# ProPrj_ct_mini_board_2024-09-02.net
KiCad netlist of a schematic drawn in EasyEDA Pro
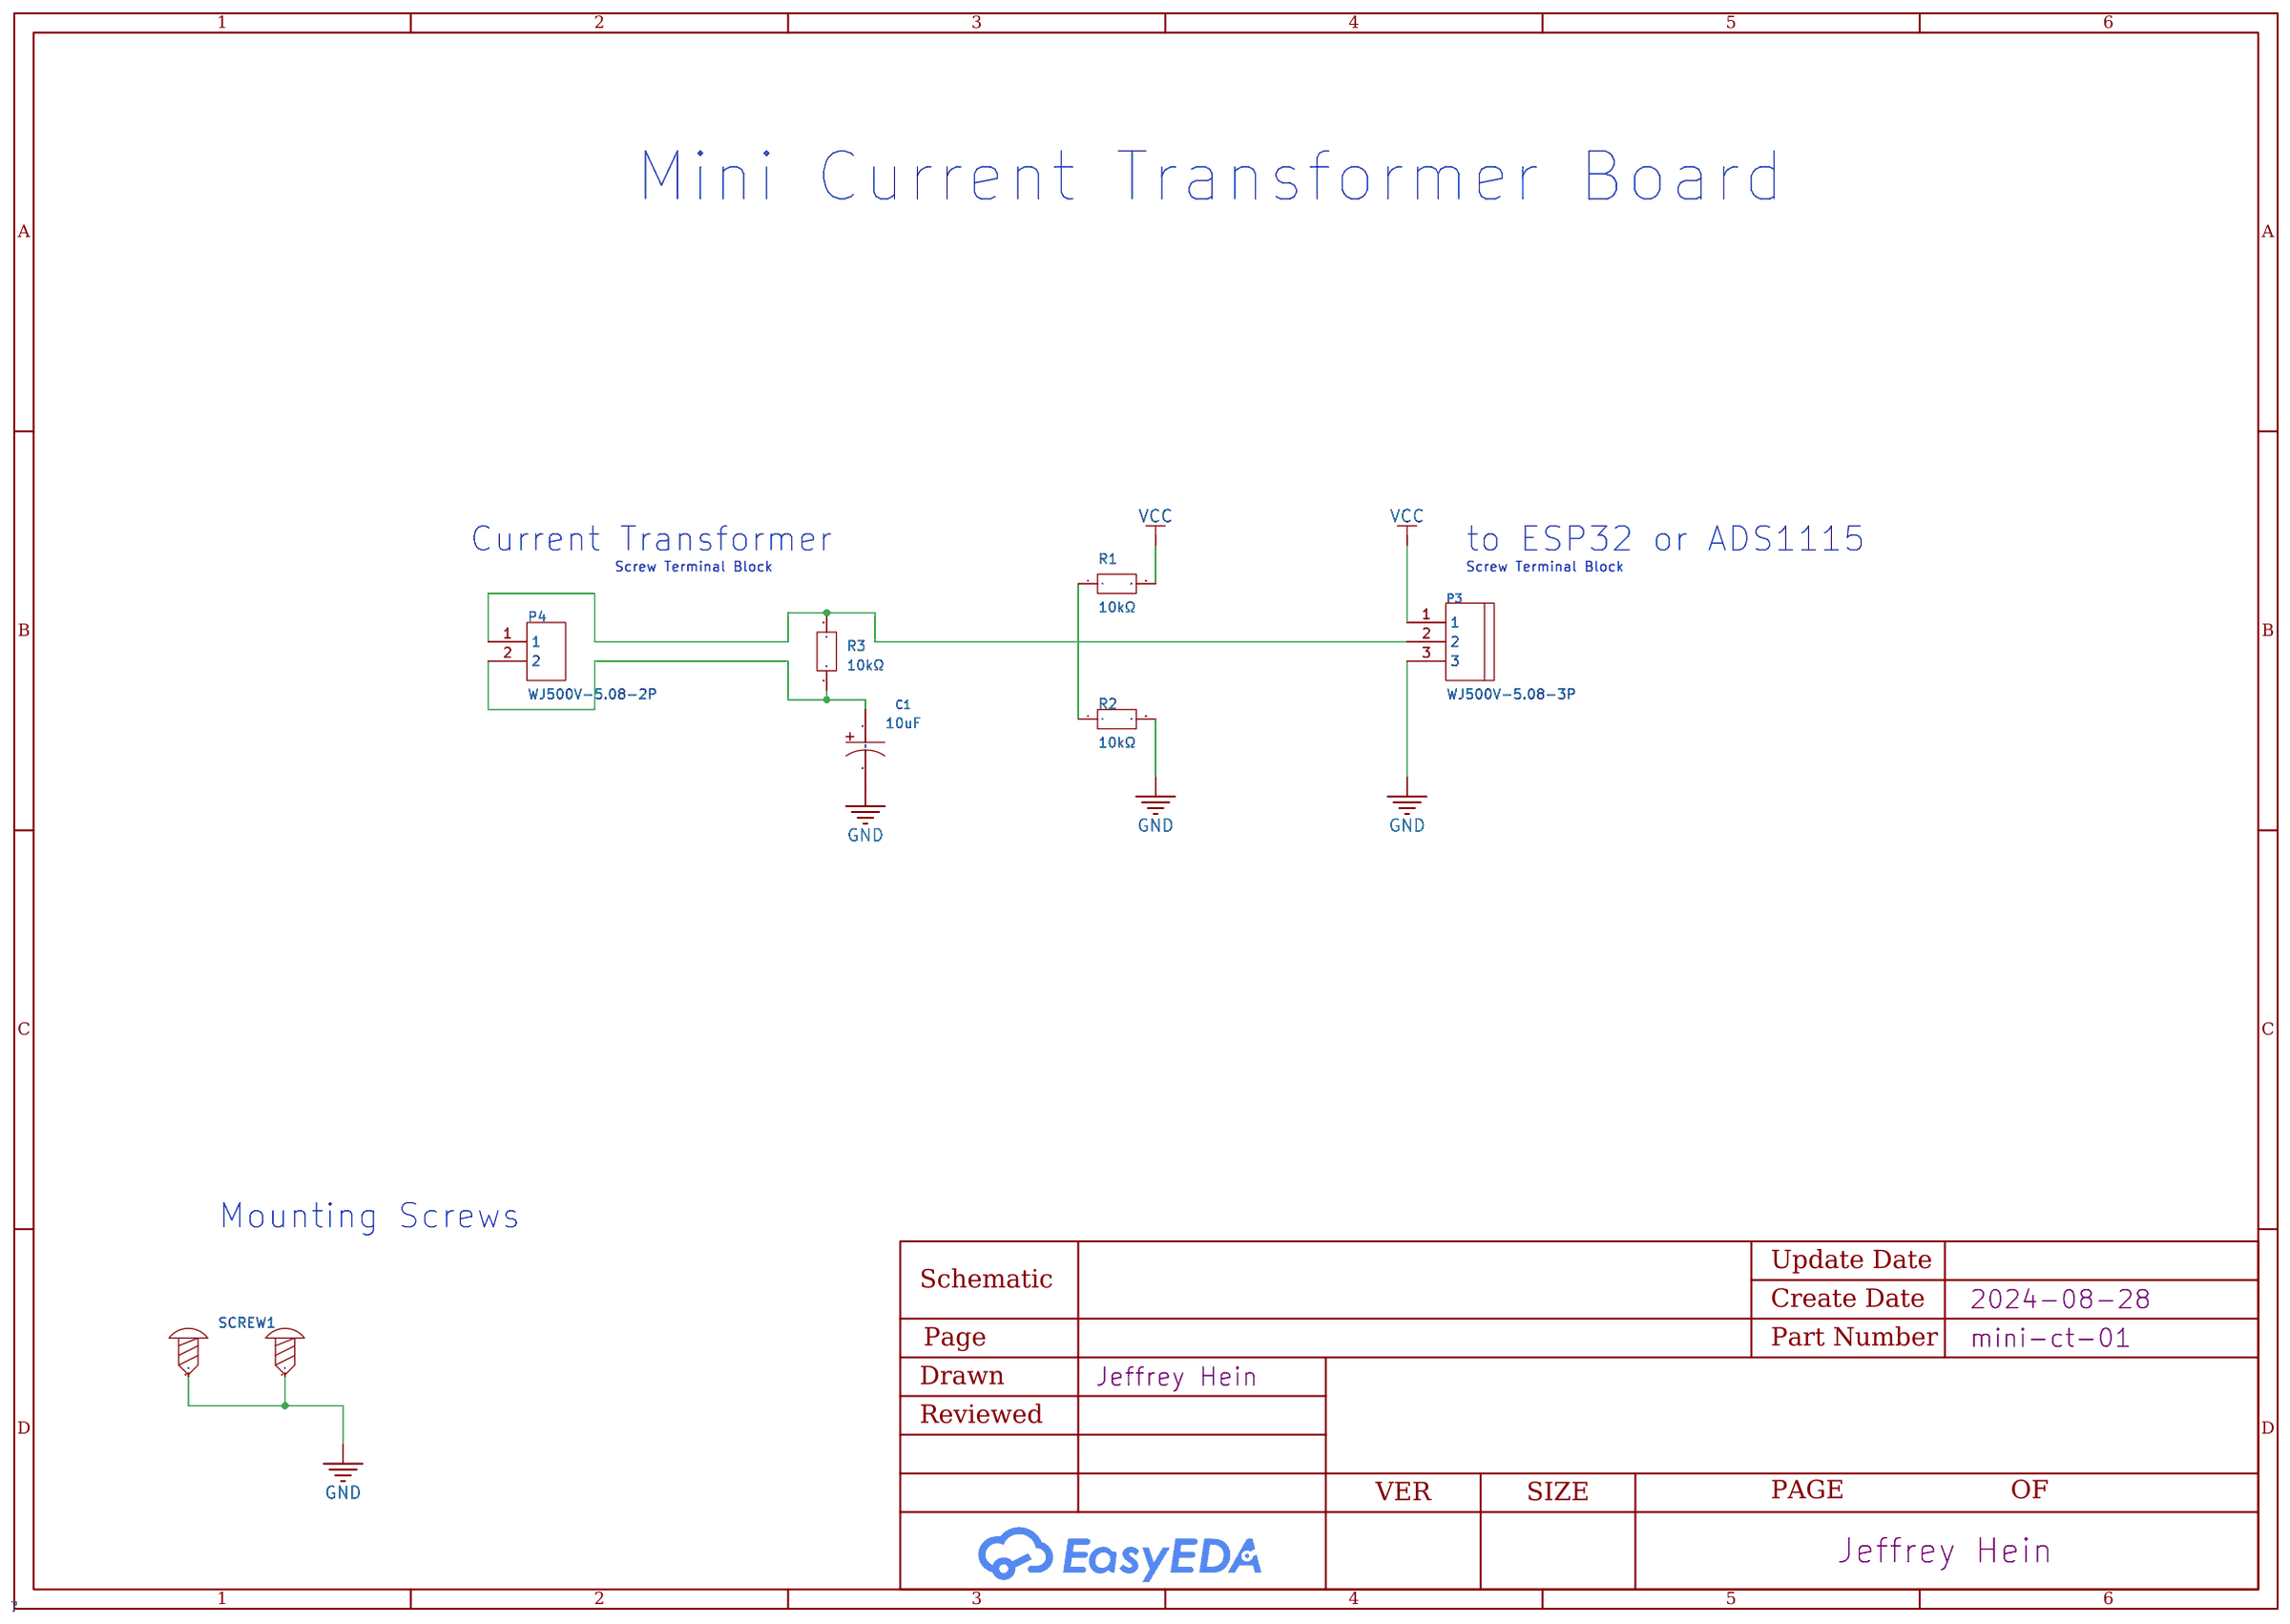
[diagram p0: schematic sheet]

(export (version "E")
  (design (tool "Eeschema 10.0.6"))
  (components
    (comp (ref "C1")
      (value "10uF")
      (footprint "easyedapro:CAP-TH_BD5.0-P5.00-D1.0-FD")
      (fields
        (field (name "Manufacturer Part") "UVZ1C100MDD1TA")
        (field (name "Manufacturer") "Nichicon(尼吉康)")
      )
      (libsource (lib "easyedapro") (part "UVZ1C100MDD1TA"))
    )
    (comp (ref "P3")
      (value "WJ500V-5.08-3P")
      (footprint "easyedapro:CONN-TH_3P-P5.00_WJ500V-5.08-3P")
      (fields (field (name "Manufacturer") "KANGNEX(康奈克斯电气)"))
      (libsource (lib "easyedapro") (part "WJ500V-5.08-3P-14-00A"))
    )
    (comp (ref "P4")
      (value "WJ500V-5.08-2P")
      (footprint "easyedapro:CONN-TH_2P-P5.00_WJ500V-5.08-2P")
      (fields (field (name "Manufacturer") "KANGNEX(康奈克斯电气)"))
      (libsource (lib "easyedapro") (part "WJ500V-5.08-2P-14-00A"))
    )
    (comp (ref "R1")
      (value "10kΩ")
      (footprint "easyedapro:RES-TH_BD2.4-L6.3-P10.30-D0.6")
      (fields
        (field (name "Manufacturer Part") "RN1/4W10KFT/BA1")
        (field (name "Manufacturer") "Tyohm(幸亚电阻)")
      )
      (libsource (lib "easyedapro") (part "RN 1/4W 10K F T/B A1"))
    )
    (comp (ref "R2")
      (value "10kΩ")
      (footprint "easyedapro:RES-TH_BD2.4-L6.3-P10.30-D0.6")
      (fields
        (field (name "Manufacturer Part") "RN1/4W10KFT/BA1")
        (field (name "Manufacturer") "Tyohm(幸亚电阻)")
      )
      (libsource (lib "easyedapro") (part "RN 1/4W 10K F T/B A1"))
    )
    (comp (ref "R3")
      (value "10kΩ")
      (footprint "easyedapro:RES-TH_BD2.4-L6.3-P10.30-D0.6")
      (fields
        (field (name "Manufacturer Part") "RN1/4W10KFT/BA1")
        (field (name "Manufacturer") "Tyohm(幸亚电阻)")
      )
      (libsource (lib "easyedapro") (part "RN 1/4W 10K F T/B A1"))
    )
    (comp (ref "SCREW1")
      (value "~")
      (footprint "easyedapro:Screw-Hole-M2")
      (libsource (lib "easyedapro") (part "Screw-Hole"))
    )
    (comp (ref "SCREW2")
      (value "~")
      (footprint "easyedapro:Screw-Hole-M2")
      (libsource (lib "easyedapro") (part "Screw-Hole"))
    )
  )
  (nets
    (net (code "1") (name "GND") (class "Default")
      (node (ref "C1") (pin "2") (pinfunction "2_2") (pintype "input"))
      (node (ref "P3") (pin "3") (pinfunction "3_3") (pintype "input"))
      (node (ref "R2") (pin "2") (pinfunction "2_2") (pintype "unspecified"))
      (node (ref "SCREW1") (pin "1") (pinfunction "1_1") (pintype "input"))
      (node (ref "SCREW2") (pin "1") (pinfunction "1_1") (pintype "input"))
    )
    (net (code "2") (name "Net-(C1-Pad1)") (class "Default")
      (node (ref "C1") (pin "1") (pinfunction "1_1") (pintype "input"))
      (node (ref "P4") (pin "2") (pinfunction "2_2") (pintype "unspecified"))
      (node (ref "R3") (pin "1") (pinfunction "1_1") (pintype "unspecified"))
    )
    (net (code "3") (name "Net-(P3-Pad2)") (class "Default")
      (node (ref "P3") (pin "2") (pinfunction "2_2") (pintype "input"))
      (node (ref "P4") (pin "1") (pinfunction "1_1") (pintype "unspecified"))
      (node (ref "R3") (pin "2") (pinfunction "2_2") (pintype "unspecified"))
    )
    (net (code "4") (name "Net-(R1-Pad1)") (class "Default")
      (node (ref "R1") (pin "1") (pinfunction "1_1") (pintype "unspecified"))
      (node (ref "R2") (pin "1") (pinfunction "1_1") (pintype "unspecified"))
    )
    (net (code "5") (name "VCC") (class "Default")
      (node (ref "P3") (pin "1") (pinfunction "1_1") (pintype "input"))
      (node (ref "R1") (pin "2") (pinfunction "2_2") (pintype "unspecified"))
    )
  )
)
